# Sheet1.net
KiCad netlist of a schematic drawn in Altium Designer
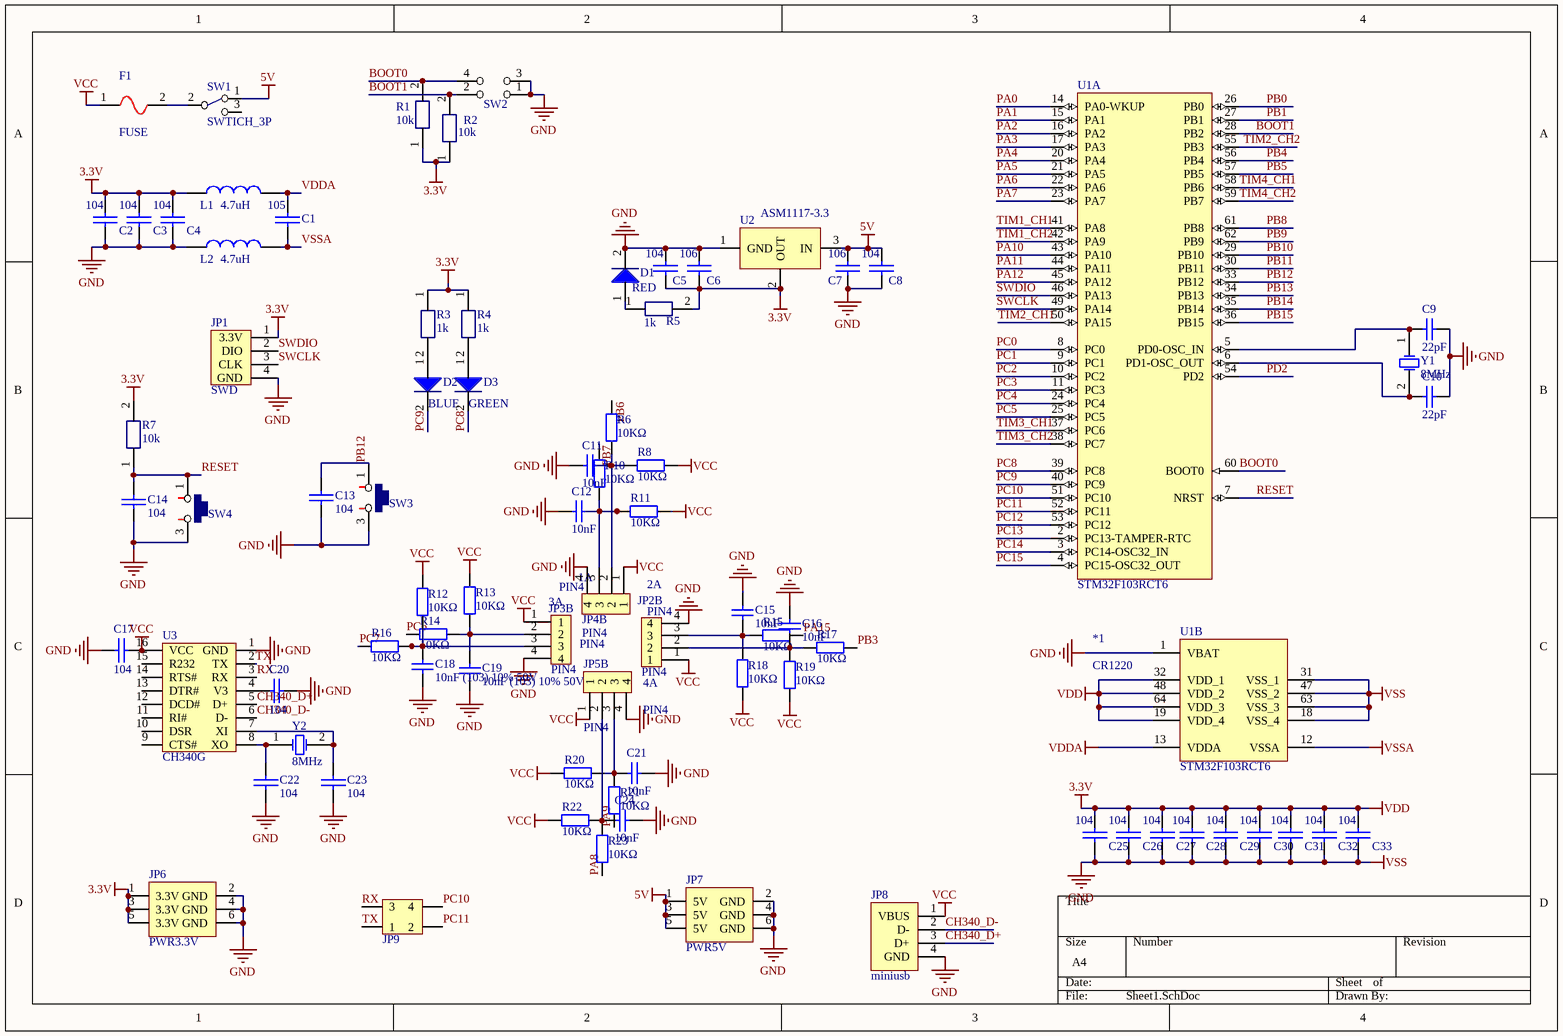
[diagram p0: Sheet1.SchDoc]

(export (version "E")
  (design (tool "Eeschema 10.0.6"))
  (components
    (comp (ref "*1") (value "CR1220") (libsource (lib "Schlib1") (part "CR1220")))
    (comp (ref "1") (value "PIN4") (libsource (lib "") (part "PIN4_2")))
    (comp (ref "2") (value "PIN4") (libsource (lib "") (part "PIN4_1")))
    (comp (ref "3") (value "PIN4") (libsource (lib "编码器Schlib1") (part "PIN4")))
    (comp (ref "4") (value "PIN4") (libsource (lib "") (part "PIN4_2")))
    (comp (ref "C1")
      (value "0805c")
      (footprint "0805C")
      (fields (field (name "ALTIUM_UNNAMED_3") "105"))
      (libsource (lib "CORE") (part "0805c"))
    )
    (comp (ref "C2")
      (value "0805c")
      (footprint "0805C")
      (fields (field (name "ALTIUM_UNNAMED_2") "104"))
      (libsource (lib "CORE") (part "0805c"))
    )
    (comp (ref "C3")
      (value "0805c")
      (footprint "0805C")
      (fields (field (name "ALTIUM_UNNAMED_2") "104"))
      (libsource (lib "CORE") (part "0805c"))
    )
    (comp (ref "C4")
      (value "0805c")
      (footprint "0805C")
      (fields (field (name "ALTIUM_UNNAMED_2") "104"))
      (libsource (lib "CORE") (part "0805c"))
    )
    (comp (ref "C5")
      (value "0805c")
      (footprint "0805C")
      (fields (field (name "ALTIUM_UNNAMED_2") "104"))
      (libsource (lib "CORE") (part "0805c"))
    )
    (comp (ref "C6")
      (value "0805c")
      (footprint "0805C")
      (fields (field (name "ALTIUM_UNNAMED_3") "106"))
      (libsource (lib "CORE") (part "0805c"))
    )
    (comp (ref "C7")
      (value "0805c")
      (footprint "0805C")
      (fields (field (name "ALTIUM_UNNAMED_3") "106"))
      (libsource (lib "CORE") (part "0805c"))
    )
    (comp (ref "C8")
      (value "0805c")
      (footprint "0805C")
      (fields (field (name "ALTIUM_UNNAMED_2") "104"))
      (libsource (lib "CORE") (part "0805c"))
    )
    (comp (ref "C9")
      (value "22pF")
      (footprint "0805C")
      (description "贴片电容")
      (libsource (lib "Cap") (part "0805 22pF (220) 5% 50V"))
    )
    (comp (ref "C10")
      (value "22pF")
      (footprint "0805C")
      (description "贴片电容")
      (libsource (lib "Cap") (part "0805 22pF (220) 5% 50V"))
    )
    (comp (ref "C11")
      (value "10nF")
      (footprint "0805C")
      (description "贴片电容")
      (libsource (lib "Cap") (part "0805 10nF (103) 10% 50V"))
    )
    (comp (ref "C12")
      (value "10nF")
      (footprint "0805C")
      (description "贴片电容")
      (libsource (lib "Cap") (part "0805 10nF (103) 10% 50V"))
    )
    (comp (ref "C13")
      (value "0805c")
      (footprint "0805C")
      (fields (field (name "ALTIUM_UNNAMED_2") "104"))
      (libsource (lib "CORE") (part "0805c"))
    )
    (comp (ref "C14")
      (value "0805c")
      (footprint "0805C")
      (fields (field (name "ALTIUM_UNNAMED_2") "104"))
      (libsource (lib "CORE") (part "0805c"))
    )
    (comp (ref "C15")
      (value "10nF")
      (footprint "0805C")
      (description "贴片电容")
      (libsource (lib "Cap") (part "0805 10nF (103) 10% 50V"))
    )
    (comp (ref "C16")
      (value "10nF")
      (footprint "0805C")
      (description "贴片电容")
      (libsource (lib "Cap") (part "0805 10nF (103) 10% 50V"))
    )
    (comp (ref "C17")
      (value "0805c")
      (footprint "0805C")
      (fields (field (name "ALTIUM_UNNAMED_2") "104"))
      (libsource (lib "CORE") (part "0805c"))
    )
    (comp (ref "C18")
      (value "10nF (103) 10% 50V")
      (footprint "0805C")
      (description "贴片电容")
      (libsource (lib "Cap") (part "0805 10nF (103) 10% 50V"))
    )
    (comp (ref "C19")
      (value "10nF (103) 10% 50V")
      (footprint "0805C")
      (description "贴片电容")
      (libsource (lib "Cap") (part "0805 10nF (103) 10% 50V"))
    )
    (comp (ref "C20")
      (value "0805c")
      (footprint "0805C")
      (fields (field (name "ALTIUM_UNNAMED_2") "104"))
      (libsource (lib "CORE") (part "0805c"))
    )
    (comp (ref "C21")
      (value "10nF")
      (footprint "0805C")
      (description "贴片电容")
      (libsource (lib "Cap") (part "0805 10nF (103) 10% 50V"))
    )
    (comp (ref "C22")
      (value "0805c")
      (footprint "0805C")
      (fields (field (name "ALTIUM_UNNAMED_2") "104"))
      (libsource (lib "CORE") (part "0805c"))
    )
    (comp (ref "C23")
      (value "0805c")
      (footprint "0805C")
      (fields (field (name "ALTIUM_UNNAMED_2") "104"))
      (libsource (lib "CORE") (part "0805c"))
    )
    (comp (ref "C24")
      (value "10nF")
      (footprint "0805C")
      (description "贴片电容")
      (libsource (lib "Cap") (part "0805 10nF (103) 10% 50V"))
    )
    (comp (ref "C25")
      (value "0805c")
      (footprint "0805C")
      (fields (field (name "ALTIUM_UNNAMED_2") "104"))
      (libsource (lib "CORE") (part "0805c"))
    )
    (comp (ref "C26")
      (value "0805c")
      (footprint "0805C")
      (fields (field (name "ALTIUM_UNNAMED_2") "104"))
      (libsource (lib "CORE") (part "0805c"))
    )
    (comp (ref "C27")
      (value "0805c")
      (footprint "0805C")
      (fields (field (name "ALTIUM_UNNAMED_2") "104"))
      (libsource (lib "CORE") (part "0805c"))
    )
    (comp (ref "C28")
      (value "0805c")
      (footprint "0805C")
      (fields (field (name "ALTIUM_UNNAMED_2") "104"))
      (libsource (lib "CORE") (part "0805c"))
    )
    (comp (ref "C29")
      (value "0805c")
      (footprint "0805C")
      (fields (field (name "ALTIUM_UNNAMED_2") "104"))
      (libsource (lib "CORE") (part "0805c"))
    )
    (comp (ref "C30")
      (value "0805c")
      (footprint "0805C")
      (fields (field (name "ALTIUM_UNNAMED_2") "104"))
      (libsource (lib "CORE") (part "0805c"))
    )
    (comp (ref "C31")
      (value "0805c")
      (footprint "0805C")
      (fields (field (name "ALTIUM_UNNAMED_2") "104"))
      (libsource (lib "CORE") (part "0805c"))
    )
    (comp (ref "C32")
      (value "0805c")
      (footprint "0805C")
      (fields (field (name "ALTIUM_UNNAMED_2") "104"))
      (libsource (lib "CORE") (part "0805c"))
    )
    (comp (ref "C33")
      (value "0805c")
      (footprint "0805C")
      (fields (field (name "ALTIUM_UNNAMED_2") "104"))
      (libsource (lib "CORE") (part "0805c"))
    )
    (comp (ref "D1")
      (value "LED")
      (footprint "0805D")
      (fields (field (name "ALTIUM_UNNAMED_1") "RED"))
      (libsource (lib "CORE") (part "LED"))
    )
    (comp (ref "D2")
      (value "LED")
      (footprint "0805D")
      (fields (field (name "ALTIUM_UNNAMED_1") "BLUE"))
      (libsource (lib "CORE") (part "LED"))
    )
    (comp (ref "D3")
      (value "LED")
      (footprint "0805D")
      (fields (field (name "ALTIUM_UNNAMED_1") "GREEN"))
      (libsource (lib "CORE") (part "LED"))
    )
    (comp (ref "F1") (value "FUSE") (footprint "1206R") (libsource (lib "CORE") (part "FUSE")))
    (comp (ref "JP1") (value "SWD") (footprint "SWD") (libsource (lib "CORE") (part "SWD")))
    (comp (ref "JP2") (value "PIN4") (footprint "HDR1X4") (libsource (lib "") (part "PIN4_1")))
    (comp (ref "JP3") (value "PIN4") (footprint "HDR1X4") (libsource (lib "") (part "PIN4_2")))
    (comp (ref "JP4") (value "PIN4") (footprint "HDR1X4") (libsource (lib "编码器Schlib1") (part "PIN4")))
    (comp (ref "JP5") (value "PIN4") (footprint "HDR1X4") (libsource (lib "") (part "PIN4_3")))
    (comp (ref "JP6") (value "PWR3.3V") (footprint "PWR") (libsource (lib "CORE") (part "PWR3.3V")))
    (comp (ref "JP7") (value "PWR5V") (footprint "PWR") (libsource (lib "CORE") (part "PWR5V")))
    (comp (ref "JP8")
      (value "miniusb")
      (footprint "MICRO-USB-SMD_MICROXNJ")
      (libsource (lib "STM32F4") (part "miniusb"))
    )
    (comp (ref "JP9") (value "2*2") (footprint "CON20VP2R54-2X2TM") (libsource (lib "STM32F4") (part "2*2")))
    (comp (ref "L1")
      (value "0805L")
      (footprint "0805L")
      (fields (field (name "ALTIUM_UNNAMED_1") "4.7uH"))
      (libsource (lib "CORE") (part "0805L"))
    )
    (comp (ref "L2")
      (value "0805L")
      (footprint "0805L")
      (fields (field (name "ALTIUM_UNNAMED_1") "4.7uH"))
      (libsource (lib "CORE") (part "0805L"))
    )
    (comp (ref "R1")
      (value "0805r")
      (footprint "0805R")
      (fields (field (name "ALTIUM_UNNAMED_4") "10k"))
      (libsource (lib "CORE") (part "0805r"))
    )
    (comp (ref "R2")
      (value "0805r")
      (footprint "0805R")
      (fields (field (name "ALTIUM_UNNAMED_4") "10k"))
      (libsource (lib "CORE") (part "0805r"))
    )
    (comp (ref "R3")
      (value "0805r")
      (footprint "0805R")
      (fields (field (name "ALTIUM_UNNAMED_3") "1k"))
      (libsource (lib "CORE") (part "0805r"))
    )
    (comp (ref "R4")
      (value "0805r")
      (footprint "0805R")
      (fields (field (name "ALTIUM_UNNAMED_3") "1k"))
      (libsource (lib "CORE") (part "0805r"))
    )
    (comp (ref "R5")
      (value "0805r")
      (footprint "0805R")
      (fields (field (name "ALTIUM_UNNAMED_3") "1k"))
      (libsource (lib "CORE") (part "0805r"))
    )
    (comp (ref "R6")
      (value "10KΩ")
      (footprint "0805R")
      (description "贴片电阻")
      (libsource (lib "") (part "0805 10KΩ (1002) 1%_1"))
    )
    (comp (ref "R7")
      (value "0805r")
      (footprint "0805R")
      (fields (field (name "ALTIUM_UNNAMED_1") "10k"))
      (libsource (lib "CORE") (part "0805r"))
    )
    (comp (ref "R8")
      (value "10KΩ")
      (footprint "0805R")
      (description "贴片电阻")
      (libsource (lib "") (part "0805 10KΩ (1002) 1%_2"))
    )
    (comp (ref "R10")
      (value "10KΩ")
      (footprint "0805R")
      (description "贴片电阻")
      (libsource (lib "") (part "0805 10KΩ (1002) 1%_1"))
    )
    (comp (ref "R11")
      (value "10KΩ")
      (footprint "0805R")
      (description "贴片电阻")
      (libsource (lib "") (part "0805 10KΩ (1002) 1%_2"))
    )
    (comp (ref "R12")
      (value "10KΩ")
      (footprint "0805R")
      (description "贴片电阻")
      (libsource (lib "RES") (part "0805 10KΩ (1002) 1%"))
    )
    (comp (ref "R13")
      (value "10KΩ")
      (footprint "0805R")
      (description "贴片电阻")
      (libsource (lib "") (part "0805 10KΩ (1002) 1%_1"))
    )
    (comp (ref "R14")
      (value "10KΩ")
      (footprint "0805R")
      (description "贴片电阻")
      (libsource (lib "") (part "0805 10KΩ (1002) 1%_3"))
    )
    (comp (ref "R15")
      (value "10KΩ")
      (footprint "0805R")
      (description "贴片电阻")
      (libsource (lib "") (part "0805 10KΩ (1002) 1%_3"))
    )
    (comp (ref "R16")
      (value "10KΩ")
      (footprint "0805R")
      (description "贴片电阻")
      (libsource (lib "") (part "0805 10KΩ (1002) 1%_3"))
    )
    (comp (ref "R17")
      (value "10KΩ")
      (footprint "0805R")
      (description "贴片电阻")
      (libsource (lib "") (part "0805 10KΩ (1002) 1%_3"))
    )
    (comp (ref "R18")
      (value "10KΩ")
      (footprint "0805R")
      (description "贴片电阻")
      (libsource (lib "RES") (part "0805 10KΩ (1002) 1%"))
    )
    (comp (ref "R19")
      (value "10KΩ")
      (footprint "0805R")
      (description "贴片电阻")
      (libsource (lib "") (part "0805 10KΩ (1002) 1%_1"))
    )
    (comp (ref "R20")
      (value "10KΩ")
      (footprint "0805R")
      (description "贴片电阻")
      (libsource (lib "") (part "0805 10KΩ (1002) 1%_3"))
    )
    (comp (ref "R21")
      (value "10KΩ")
      (footprint "0805R")
      (description "贴片电阻")
      (libsource (lib "RES") (part "0805 10KΩ (1002) 1%"))
    )
    (comp (ref "R22")
      (value "10KΩ")
      (footprint "0805R")
      (description "贴片电阻")
      (libsource (lib "") (part "0805 10KΩ (1002) 1%_3"))
    )
    (comp (ref "R23")
      (value "10KΩ")
      (footprint "0805R")
      (description "贴片电阻")
      (libsource (lib "RES") (part "0805 10KΩ (1002) 1%"))
    )
    (comp (ref "SW1") (value "SWTICH_3P") (footprint "SWITCH_3P") (libsource (lib "CORE") (part "SWTICH_3P")))
    (comp (ref "SW2")
      (value "SW_BOOT")
      (footprint "CON20VP2R54-2X2TM")
      (libsource (lib "CORE") (part "SW_BOOT"))
    )
    (comp (ref "SW3")
      (value "KEY")
      (footprint "SW-SMD_L6.1-W3.6-LS8.0")
      (libsource (lib "CORE") (part "KEY_4P"))
    )
    (comp (ref "SW4")
      (value "KEY")
      (footprint "SW-SMD_L6.1-W3.6-LS8.0")
      (libsource (lib "CORE") (part "KEY_4P"))
    )
    (comp (ref "U1")
      (value "STM32F103RCT6")
      (footprint "PCBComponent_1")
      (libsource (lib "STMicroelectronics STM32 F1") (part "STM32F103RCT6"))
    )
    (comp (ref "U2")
      (value "ASM1117-3.3")
      (footprint "SOT223_N")
      (libsource (lib "CORE") (part "ASM1117-3.3"))
    )
    (comp (ref "U3") (value "CH340G") (footprint "SOP16") (libsource (lib "CORE") (part "CH340G")))
    (comp (ref "Y1")
      (value "8MHz")
      (footprint "HC-49US_L11.5-W4.5-P4.88")
      (description "贴片晶振")
      (libsource (lib "CrystalOscillator") (part "SMD-5032_2P 8MHz 20ppm 20pF"))
    )
    (comp (ref "Y2")
      (value "8MHz")
      (footprint "HC-49S_L11.4-W4.8")
      (description "贴片晶振")
      (libsource (lib "CrystalOscillator") (part "SMD-5032_2P 8MHz 20ppm 20pF"))
    )
  )
  (nets
    (net (code "1") (name "/BOOT0") (class "Default")
      (node (ref "R1") (pin "2") (pinfunction "2_2") (pintype "passive"))
      (node (ref "SW2") (pin "4") (pinfunction "4_4") (pintype "passive"))
      (node (ref "U1") (pin "60") (pinfunction "BOOT0_60") (pintype "input"))
    )
    (net (code "2") (name "/BOOT1") (class "Default")
      (node (ref "R2") (pin "2") (pinfunction "2_2") (pintype "passive"))
      (node (ref "SW2") (pin "2") (pinfunction "2_2") (pintype "passive"))
      (node (ref "U1") (pin "28") (pinfunction "PB2_28") (pintype "bidirectional"))
    )
    (net (code "3") (name "/CH340_D+") (class "Default")
      (node (ref "JP8") (pin "3") (pinfunction "D+_3") (pintype "passive"))
      (node (ref "U3") (pin "5") (pinfunction "D+_5") (pintype "passive"))
    )
    (net (code "4") (name "/CH340_D-") (class "Default")
      (node (ref "JP8") (pin "2") (pinfunction "D-_2") (pintype "passive"))
      (node (ref "U3") (pin "6") (pinfunction "D-_6") (pintype "passive"))
    )
    (net (code "5") (name "/PA0") (class "Default")
      (node (ref "U1") (pin "14") (pinfunction "PA0-WKUP_14") (pintype "bidirectional"))
    )
    (net (code "6") (name "/PA1") (class "Default")
      (node (ref "U1") (pin "15") (pinfunction "PA1_15") (pintype "bidirectional"))
    )
    (net (code "7") (name "/PA2") (class "Default")
      (node (ref "U1") (pin "16") (pinfunction "PA2_16") (pintype "bidirectional"))
    )
    (net (code "8") (name "/PA3") (class "Default")
      (node (ref "U1") (pin "17") (pinfunction "PA3_17") (pintype "bidirectional"))
    )
    (net (code "9") (name "/PA4") (class "Default")
      (node (ref "U1") (pin "20") (pinfunction "PA4_20") (pintype "bidirectional"))
    )
    (net (code "10") (name "/PA5") (class "Default")
      (node (ref "U1") (pin "21") (pinfunction "PA5_21") (pintype "bidirectional"))
    )
    (net (code "11") (name "/PA6") (class "Default")
      (node (ref "U1") (pin "22") (pinfunction "PA6_22") (pintype "bidirectional"))
    )
    (net (code "12") (name "/PA7") (class "Default")
      (node (ref "U1") (pin "23") (pinfunction "PA7_23") (pintype "bidirectional"))
    )
    (net (code "13") (name "/PA8") (class "Default")
      (node (ref "R23") (pin "2") (pinfunction "2_2") (pintype "passive"))
    )
    (net (code "14") (name "/PA9") (class "Default")
      (node (ref "R21") (pin "2") (pinfunction "2_2") (pintype "passive"))
    )
    (net (code "15") (name "/PA10") (class "Default")
      (node (ref "U1") (pin "43") (pinfunction "PA10_43") (pintype "bidirectional"))
    )
    (net (code "16") (name "/PA11") (class "Default")
      (node (ref "U1") (pin "44") (pinfunction "PA11_44") (pintype "bidirectional"))
    )
    (net (code "17") (name "/PA12") (class "Default")
      (node (ref "U1") (pin "45") (pinfunction "PA12_45") (pintype "bidirectional"))
    )
    (net (code "18") (name "/PA15") (class "Default")
      (node (ref "R15") (pin "2") (pinfunction "2_2") (pintype "passive"))
    )
    (net (code "19") (name "/PB0") (class "Default")
      (node (ref "U1") (pin "26") (pinfunction "PB0_26") (pintype "bidirectional"))
    )
    (net (code "20") (name "/PB1") (class "Default")
      (node (ref "U1") (pin "27") (pinfunction "PB1_27") (pintype "bidirectional"))
    )
    (net (code "21") (name "/PB3") (class "Default")
      (node (ref "R17") (pin "2") (pinfunction "2_2") (pintype "passive"))
    )
    (net (code "22") (name "/PB4") (class "Default")
      (node (ref "U1") (pin "56") (pinfunction "PB4_56") (pintype "bidirectional"))
    )
    (net (code "23") (name "/PB5") (class "Default")
      (node (ref "U1") (pin "57") (pinfunction "PB5_57") (pintype "bidirectional"))
    )
    (net (code "24") (name "/PB6") (class "Default")
      (node (ref "R6") (pin "2") (pinfunction "2_2") (pintype "passive"))
    )
    (net (code "25") (name "/PB7") (class "Default")
      (node (ref "R10") (pin "2") (pinfunction "2_2") (pintype "passive"))
    )
    (net (code "26") (name "/PB8") (class "Default")
      (node (ref "U1") (pin "61") (pinfunction "PB8_61") (pintype "bidirectional"))
    )
    (net (code "27") (name "/PB9") (class "Default")
      (node (ref "U1") (pin "62") (pinfunction "PB9_62") (pintype "bidirectional"))
    )
    (net (code "28") (name "/PB10") (class "Default")
      (node (ref "U1") (pin "29") (pinfunction "PB10_29") (pintype "bidirectional"))
    )
    (net (code "29") (name "/PB11") (class "Default")
      (node (ref "U1") (pin "30") (pinfunction "PB11_30") (pintype "bidirectional"))
    )
    (net (code "30") (name "/PB12") (class "Default")
      (node (ref "C13") (pin "1") (pinfunction "1_1") (pintype "passive"))
      (node (ref "SW3") (pin "1") (pintype "passive"))
      (node (ref "U1") (pin "33") (pinfunction "PB12_33") (pintype "bidirectional"))
    )
    (net (code "31") (name "/PB13") (class "Default")
      (node (ref "U1") (pin "34") (pinfunction "PB13_34") (pintype "bidirectional"))
    )
    (net (code "32") (name "/PB14") (class "Default")
      (node (ref "U1") (pin "35") (pinfunction "PB14_35") (pintype "bidirectional"))
    )
    (net (code "33") (name "/PB15") (class "Default")
      (node (ref "U1") (pin "36") (pinfunction "PB15_36") (pintype "bidirectional"))
    )
    (net (code "34") (name "/PC0") (class "Default")
      (node (ref "U1") (pin "8") (pinfunction "PC0_8") (pintype "bidirectional"))
    )
    (net (code "35") (name "/PC1") (class "Default")
      (node (ref "U1") (pin "9") (pinfunction "PC1_9") (pintype "bidirectional"))
    )
    (net (code "36") (name "/PC2") (class "Default")
      (node (ref "U1") (pin "10") (pinfunction "PC2_10") (pintype "bidirectional"))
    )
    (net (code "37") (name "/PC3") (class "Default")
      (node (ref "U1") (pin "11") (pinfunction "PC3_11") (pintype "bidirectional"))
    )
    (net (code "38") (name "/PC4") (class "Default")
      (node (ref "U1") (pin "24") (pinfunction "PC4_24") (pintype "bidirectional"))
    )
    (net (code "39") (name "/PC5") (class "Default")
      (node (ref "U1") (pin "25") (pinfunction "PC5_25") (pintype "bidirectional"))
    )
    (net (code "40") (name "/PC6") (class "Default")
      (node (ref "R14") (pin "1") (pinfunction "1_1") (pintype "passive"))
    )
    (net (code "41") (name "/PC7") (class "Default")
      (node (ref "R16") (pin "1") (pinfunction "1_1") (pintype "passive"))
    )
    (net (code "42") (name "/PC8") (class "Default")
      (node (ref "D3") (pin "2") (pinfunction "2_2") (pintype "passive"))
      (node (ref "U1") (pin "39") (pinfunction "PC8_39") (pintype "bidirectional"))
    )
    (net (code "43") (name "/PC9") (class "Default")
      (node (ref "D2") (pin "2") (pinfunction "2_2") (pintype "passive"))
      (node (ref "U1") (pin "40") (pinfunction "PC9_40") (pintype "bidirectional"))
    )
    (net (code "44") (name "/PC10") (class "Default")
      (node (ref "JP9") (pin "4") (pinfunction "4_4") (pintype "passive"))
      (node (ref "U1") (pin "51") (pinfunction "PC10_51") (pintype "bidirectional"))
    )
    (net (code "45") (name "/PC11") (class "Default")
      (node (ref "JP9") (pin "2") (pinfunction "2_2") (pintype "passive"))
      (node (ref "U1") (pin "52") (pinfunction "PC11_52") (pintype "bidirectional"))
    )
    (net (code "46") (name "/PC12") (class "Default")
      (node (ref "U1") (pin "53") (pinfunction "PC12_53") (pintype "bidirectional"))
    )
    (net (code "47") (name "/PC13") (class "Default")
      (node (ref "U1") (pin "2") (pinfunction "PC13-TAMPER-RTC_2") (pintype "bidirectional"))
    )
    (net (code "48") (name "/PC14") (class "Default")
      (node (ref "U1") (pin "3") (pinfunction "PC14-OSC32_IN_3") (pintype "bidirectional"))
    )
    (net (code "49") (name "/PC15") (class "Default")
      (node (ref "U1") (pin "4") (pinfunction "PC15-OSC32_OUT_4") (pintype "bidirectional"))
    )
    (net (code "50") (name "/PD2") (class "Default")
      (node (ref "U1") (pin "54") (pinfunction "PD2_54") (pintype "bidirectional"))
    )
    (net (code "51") (name "/RESET") (class "Default")
      (node (ref "C14") (pin "1") (pinfunction "1_1") (pintype "passive"))
      (node (ref "R7") (pin "1") (pinfunction "1_1") (pintype "passive"))
      (node (ref "SW4") (pin "1") (pintype "passive"))
      (node (ref "U1") (pin "7") (pinfunction "NRST_7") (pintype "bidirectional"))
    )
    (net (code "52") (name "/RX") (class "Default")
      (node (ref "JP9") (pin "3") (pinfunction "3_3") (pintype "passive"))
      (node (ref "U3") (pin "3") (pinfunction "RX_3") (pintype "passive"))
    )
    (net (code "53") (name "/SWCLK") (class "Default")
      (node (ref "JP1") (pin "3") (pinfunction "CLK_3") (pintype "passive"))
      (node (ref "U1") (pin "49") (pinfunction "PA14_49") (pintype "bidirectional"))
    )
    (net (code "54") (name "/SWDIO") (class "Default")
      (node (ref "JP1") (pin "2") (pinfunction "DIO_2") (pintype "passive"))
      (node (ref "U1") (pin "46") (pinfunction "PA13_46") (pintype "bidirectional"))
    )
    (net (code "55") (name "/TIM1_CH1") (class "Default")
      (node (ref "U1") (pin "41") (pinfunction "PA8_41") (pintype "bidirectional"))
    )
    (net (code "56") (name "/TIM1_CH2") (class "Default")
      (node (ref "U1") (pin "42") (pinfunction "PA9_42") (pintype "bidirectional"))
    )
    (net (code "57") (name "/TIM2_CH1") (class "Default")
      (node (ref "U1") (pin "50") (pinfunction "PA15_50") (pintype "bidirectional"))
    )
    (net (code "58") (name "/TIM2_CH2") (class "Default")
      (node (ref "U1") (pin "55") (pinfunction "PB3_55") (pintype "bidirectional"))
    )
    (net (code "59") (name "/TIM3_CH1") (class "Default")
      (node (ref "U1") (pin "37") (pinfunction "PC6_37") (pintype "bidirectional"))
    )
    (net (code "60") (name "/TIM3_CH2") (class "Default")
      (node (ref "U1") (pin "38") (pinfunction "PC7_38") (pintype "bidirectional"))
    )
    (net (code "61") (name "/TIM4_CH1") (class "Default")
      (node (ref "U1") (pin "58") (pinfunction "PB6_58") (pintype "bidirectional"))
    )
    (net (code "62") (name "/TIM4_CH2") (class "Default")
      (node (ref "U1") (pin "59") (pinfunction "PB7_59") (pintype "bidirectional"))
    )
    (net (code "63") (name "/TX") (class "Default")
      (node (ref "JP9") (pin "1") (pinfunction "1_1") (pintype "passive"))
      (node (ref "U3") (pin "2") (pinfunction "TX_2") (pintype "passive"))
    )
    (net (code "64") (name "3.3V") (class "Default")
      (node (ref "C2") (pin "1") (pinfunction "1_1") (pintype "passive"))
      (node (ref "C25") (pin "1") (pinfunction "1_1") (pintype "passive"))
      (node (ref "C26") (pin "1") (pinfunction "1_1") (pintype "passive"))
      (node (ref "C27") (pin "1") (pinfunction "1_1") (pintype "passive"))
      (node (ref "C28") (pin "1") (pinfunction "1_1") (pintype "passive"))
      (node (ref "C29") (pin "1") (pinfunction "1_1") (pintype "passive"))
      (node (ref "C3") (pin "1") (pinfunction "1_1") (pintype "passive"))
      (node (ref "C30") (pin "1") (pinfunction "1_1") (pintype "passive"))
      (node (ref "C31") (pin "1") (pinfunction "1_1") (pintype "passive"))
      (node (ref "C32") (pin "1") (pinfunction "1_1") (pintype "passive"))
      (node (ref "C33") (pin "1") (pinfunction "1_1") (pintype "passive"))
      (node (ref "C4") (pin "1") (pinfunction "1_1") (pintype "passive"))
      (node (ref "C5") (pin "2") (pinfunction "2_2") (pintype "passive"))
      (node (ref "C6") (pin "2") (pinfunction "2_2") (pintype "passive"))
      (node (ref "JP1") (pin "1") (pinfunction "3.3V_1") (pintype "passive"))
      (node (ref "JP6") (pin "1") (pinfunction "3.3V_1") (pintype "passive"))
      (node (ref "JP6") (pin "3") (pinfunction "3.3V_3") (pintype "passive"))
      (node (ref "JP6") (pin "5") (pinfunction "3.3V_5") (pintype "passive"))
      (node (ref "L1") (pin "1") (pinfunction "1_1") (pintype "passive"))
      (node (ref "R1") (pin "1") (pinfunction "1_1") (pintype "passive"))
      (node (ref "R2") (pin "1") (pinfunction "1_1") (pintype "passive"))
      (node (ref "R3") (pin "1") (pinfunction "1_1") (pintype "passive"))
      (node (ref "R4") (pin "1") (pinfunction "1_1") (pintype "passive"))
      (node (ref "R5") (pin "2") (pinfunction "2_2") (pintype "passive"))
      (node (ref "R7") (pin "2") (pinfunction "2_2") (pintype "passive"))
      (node (ref "U1") (pin "19") (pinfunction "VDD_4_19") (pintype "power_in"))
      (node (ref "U1") (pin "32") (pinfunction "VDD_1_32") (pintype "power_in"))
      (node (ref "U1") (pin "48") (pinfunction "VDD_2_48") (pintype "power_in"))
      (node (ref "U1") (pin "64") (pinfunction "VDD_3_64") (pintype "power_in"))
      (node (ref "U2") (pin "2") (pinfunction "OUT_2") (pintype "passive"))
    )
    (net (code "65") (name "5V") (class "Default")
      (node (ref "C7") (pin "1") (pinfunction "1_1") (pintype "passive"))
      (node (ref "C8") (pin "1") (pinfunction "1_1") (pintype "passive"))
      (node (ref "JP7") (pin "1") (pinfunction "5V_1") (pintype "passive"))
      (node (ref "JP7") (pin "3") (pinfunction "5V_3") (pintype "passive"))
      (node (ref "JP7") (pin "5") (pinfunction "5V_5") (pintype "passive"))
      (node (ref "SW1") (pin "1") (pinfunction "1_1") (pintype "passive"))
      (node (ref "U2") (pin "3") (pinfunction "IN_3") (pintype "passive"))
    )
    (net (code "66") (name "GND") (class "Default")
      (node (ref "C10") (pin "2") (pinfunction "2_2") (pintype "passive"))
      (node (ref "C11") (pin "1") (pinfunction "1_1") (pintype "passive"))
      (node (ref "C12") (pin "1") (pinfunction "1_1") (pintype "passive"))
      (node (ref "C13") (pin "2") (pinfunction "2_2") (pintype "passive"))
      (node (ref "C14") (pin "2") (pinfunction "2_2") (pintype "passive"))
      (node (ref "C15") (pin "1") (pinfunction "1_1") (pintype "passive"))
      (node (ref "C16") (pin "2") (pinfunction "2_2") (pintype "passive"))
      (node (ref "C17") (pin "1") (pinfunction "1_1") (pintype "passive"))
      (node (ref "C18") (pin "2") (pinfunction "2_2") (pintype "passive"))
      (node (ref "C19") (pin "2") (pinfunction "2_2") (pintype "passive"))
      (node (ref "C2") (pin "2") (pinfunction "2_2") (pintype "passive"))
      (node (ref "C20") (pin "2") (pinfunction "2_2") (pintype "passive"))
      (node (ref "C21") (pin "2") (pinfunction "2_2") (pintype "passive"))
      (node (ref "C22") (pin "2") (pinfunction "2_2") (pintype "passive"))
      (node (ref "C23") (pin "2") (pinfunction "2_2") (pintype "passive"))
      (node (ref "C24") (pin "2") (pinfunction "2_2") (pintype "passive"))
      (node (ref "C25") (pin "2") (pinfunction "2_2") (pintype "passive"))
      (node (ref "C26") (pin "2") (pinfunction "2_2") (pintype "passive"))
      (node (ref "C27") (pin "2") (pinfunction "2_2") (pintype "passive"))
      (node (ref "C28") (pin "2") (pinfunction "2_2") (pintype "passive"))
      (node (ref "C29") (pin "2") (pinfunction "2_2") (pintype "passive"))
      (node (ref "C3") (pin "2") (pinfunction "2_2") (pintype "passive"))
      (node (ref "C30") (pin "2") (pinfunction "2_2") (pintype "passive"))
      (node (ref "C31") (pin "2") (pinfunction "2_2") (pintype "passive"))
      (node (ref "C32") (pin "2") (pinfunction "2_2") (pintype "passive"))
      (node (ref "C33") (pin "2") (pinfunction "2_2") (pintype "passive"))
      (node (ref "C4") (pin "2") (pinfunction "2_2") (pintype "passive"))
      (node (ref "C5") (pin "1") (pinfunction "1_1") (pintype "passive"))
      (node (ref "C6") (pin "1") (pinfunction "1_1") (pintype "passive"))
      (node (ref "C7") (pin "2") (pinfunction "2_2") (pintype "passive"))
      (node (ref "C8") (pin "2") (pinfunction "2_2") (pintype "passive"))
      (node (ref "C9") (pin "2") (pinfunction "2_2") (pintype "passive"))
      (node (ref "D1") (pin "2") (pinfunction "2_2") (pintype "passive"))
      (node (ref "JP1") (pin "4") (pinfunction "GND_4") (pintype "passive"))
      (node (ref "JP2") (pin "4") (pinfunction "4_4") (pintype "passive"))
      (node (ref "JP3") (pin "4") (pinfunction "4_4") (pintype "passive"))
      (node (ref "JP4") (pin "4") (pinfunction "4_4") (pintype "passive"))
      (node (ref "JP5") (pin "4") (pinfunction "4_4") (pintype "passive"))
      (node (ref "JP6") (pin "2") (pinfunction "GND_2") (pintype "passive"))
      (node (ref "JP6") (pin "4") (pinfunction "GND_4") (pintype "passive"))
      (node (ref "JP6") (pin "6") (pinfunction "GND_6") (pintype "passive"))
      (node (ref "JP7") (pin "2") (pinfunction "GND_2") (pintype "passive"))
      (node (ref "JP7") (pin "4") (pinfunction "GND_4") (pintype "passive"))
      (node (ref "JP7") (pin "6") (pinfunction "GND_6") (pintype "passive"))
      (node (ref "JP8") (pin "4") (pinfunction "GND_4") (pintype "passive"))
      (node (ref "L2") (pin "1") (pinfunction "1_1") (pintype "passive"))
      (node (ref "SW2") (pin "1") (pinfunction "1_1") (pintype "passive"))
      (node (ref "SW2") (pin "3") (pinfunction "3_3") (pintype "passive"))
      (node (ref "SW3") (pin "3") (pintype "passive"))
      (node (ref "SW4") (pin "3") (pintype "passive"))
      (node (ref "U1") (pin "1") (pinfunction "VBAT_1") (pintype "power_in"))
      (node (ref "U1") (pin "18") (pinfunction "VSS_4_18") (pintype "power_in"))
      (node (ref "U1") (pin "31") (pinfunction "VSS_1_31") (pintype "power_in"))
      (node (ref "U1") (pin "47") (pinfunction "VSS_2_47") (pintype "power_in"))
      (node (ref "U1") (pin "63") (pinfunction "VSS_3_63") (pintype "power_in"))
      (node (ref "U2") (pin "1") (pinfunction "GND_1") (pintype "passive"))
      (node (ref "U3") (pin "1") (pinfunction "GND_1") (pintype "passive"))
    )
    (net (code "67") (name "Net-(C11-Pad2)") (class "Default")
      (node (ref "C11") (pin "2") (pinfunction "2_2") (pintype "passive"))
      (node (ref "JP4") (pin "2") (pinfunction "2_2") (pintype "passive"))
      (node (ref "R6") (pin "1") (pinfunction "1_1") (pintype "passive"))
      (node (ref "R8") (pin "2") (pinfunction "2_2") (pintype "passive"))
    )
    (net (code "68") (name "Net-(C12-Pad2)") (class "Default")
      (node (ref "C12") (pin "2") (pinfunction "2_2") (pintype "passive"))
      (node (ref "JP4") (pin "3") (pinfunction "3_3") (pintype "passive"))
      (node (ref "R10") (pin "1") (pinfunction "1_1") (pintype "passive"))
      (node (ref "R11") (pin "2") (pinfunction "2_2") (pintype "passive"))
    )
    (net (code "69") (name "Net-(C18-Pad1)") (class "Default")
      (node (ref "C18") (pin "1") (pinfunction "1_1") (pintype "passive"))
      (node (ref "JP3") (pin "3") (pinfunction "3_3") (pintype "passive"))
      (node (ref "R12") (pin "2") (pinfunction "2_2") (pintype "passive"))
      (node (ref "R16") (pin "2") (pinfunction "2_2") (pintype "passive"))
    )
    (net (code "70") (name "Net-(C19-Pad1)") (class "Default")
      (node (ref "C19") (pin "1") (pinfunction "1_1") (pintype "passive"))
      (node (ref "JP3") (pin "2") (pinfunction "2_2") (pintype "passive"))
      (node (ref "R13") (pin "1") (pinfunction "1_1") (pintype "passive"))
      (node (ref "R14") (pin "2") (pinfunction "2_2") (pintype "passive"))
    )
    (net (code "71") (name "Net-(C21-Pad1)") (class "Default")
      (node (ref "C21") (pin "1") (pinfunction "1_1") (pintype "passive"))
      (node (ref "JP5") (pin "3") (pinfunction "3_3") (pintype "passive"))
      (node (ref "R20") (pin "2") (pinfunction "2_2") (pintype "passive"))
      (node (ref "R21") (pin "1") (pinfunction "1_1") (pintype "passive"))
    )
    (net (code "72") (name "Net-(C24-Pad1)") (class "Default")
      (node (ref "C24") (pin "1") (pinfunction "1_1") (pintype "passive"))
      (node (ref "JP5") (pin "2") (pinfunction "2_2") (pintype "passive"))
      (node (ref "R22") (pin "2") (pinfunction "2_2") (pintype "passive"))
      (node (ref "R23") (pin "1") (pinfunction "1_1") (pintype "passive"))
    )
    (net (code "73") (name "Net-(D1-Pad1)") (class "Default")
      (node (ref "D1") (pin "1") (pinfunction "1_1") (pintype "passive"))
      (node (ref "R5") (pin "1") (pinfunction "1_1") (pintype "passive"))
    )
    (net (code "74") (name "Net-(D2-Pad1)") (class "Default")
      (node (ref "D2") (pin "1") (pinfunction "1_1") (pintype "passive"))
      (node (ref "R3") (pin "2") (pinfunction "2_2") (pintype "passive"))
    )
    (net (code "75") (name "Net-(D3-Pad1)") (class "Default")
      (node (ref "D3") (pin "1") (pinfunction "1_1") (pintype "passive"))
      (node (ref "R4") (pin "2") (pinfunction "2_2") (pintype "passive"))
    )
    (net (code "76") (name "Net-(F1-Pad2)") (class "Default")
      (node (ref "F1") (pin "2") (pinfunction "2_2") (pintype "passive"))
      (node (ref "SW1") (pin "2") (pinfunction "2_2") (pintype "passive"))
    )
    (net (code "77") (name "Net-(JP2-Pad2)") (class "Default")
      (node (ref "JP2") (pin "2") (pinfunction "2_2") (pintype "passive"))
      (node (ref "R17") (pin "1") (pinfunction "1_1") (pintype "passive"))
      (node (ref "R19") (pin "2") (pinfunction "2_2") (pintype "passive"))
    )
    (net (code "78") (name "Net-(JP2-Pad3)") (class "Default")
      (node (ref "JP2") (pin "3") (pinfunction "3_3") (pintype "passive"))
      (node (ref "R15") (pin "1") (pinfunction "1_1") (pintype "passive"))
      (node (ref "R18") (pin "1") (pinfunction "1_1") (pintype "passive"))
    )
    (net (code "79") (name "Net-(U1A-PD0-OSC_IN)") (class "Default")
      (node (ref "C9") (pin "1") (pinfunction "1_1") (pintype "passive"))
      (node (ref "U1") (pin "5") (pinfunction "PD0-OSC_IN_5") (pintype "bidirectional"))
      (node (ref "Y1") (pin "1") (pinfunction "OSC1_1") (pintype "passive"))
    )
    (net (code "80") (name "Net-(U1A-PD1-OSC_OUT)") (class "Default")
      (node (ref "C10") (pin "1") (pinfunction "1_1") (pintype "passive"))
      (node (ref "U1") (pin "6") (pinfunction "PD1-OSC_OUT_6") (pintype "bidirectional"))
      (node (ref "Y1") (pin "2") (pinfunction "OSC2_2") (pintype "passive"))
    )
    (net (code "81") (name "Net-(U3-V3)") (class "Default")
      (node (ref "C20") (pin "1") (pinfunction "1_1") (pintype "passive"))
      (node (ref "U3") (pin "4") (pinfunction "V3_4") (pintype "passive"))
    )
    (net (code "82") (name "Net-(U3-XI)") (class "Default")
      (node (ref "C23") (pin "1") (pinfunction "1_1") (pintype "passive"))
      (node (ref "U3") (pin "7") (pinfunction "XI_7") (pintype "passive"))
      (node (ref "Y2") (pin "2") (pinfunction "OSC2_2") (pintype "passive"))
    )
    (net (code "83") (name "Net-(U3-XO)") (class "Default")
      (node (ref "C22") (pin "1") (pinfunction "1_1") (pintype "passive"))
      (node (ref "U3") (pin "8") (pinfunction "XO_8") (pintype "passive"))
      (node (ref "Y2") (pin "1") (pinfunction "OSC1_1") (pintype "passive"))
    )
    (net (code "84") (name "VCC") (class "Default")
      (node (ref "C17") (pin "2") (pinfunction "2_2") (pintype "passive"))
      (node (ref "F1") (pin "1") (pinfunction "1_1") (pintype "passive"))
      (node (ref "JP2") (pin "1") (pinfunction "1_1") (pintype "passive"))
      (node (ref "JP3") (pin "1") (pinfunction "1_1") (pintype "passive"))
      (node (ref "JP4") (pin "1") (pinfunction "1_1") (pintype "passive"))
      (node (ref "JP5") (pin "1") (pinfunction "1_1") (pintype "passive"))
      (node (ref "JP8") (pin "1") (pinfunction "VBUS_1") (pintype "passive"))
      (node (ref "R11") (pin "1") (pinfunction "1_1") (pintype "passive"))
      (node (ref "R12") (pin "1") (pinfunction "1_1") (pintype "passive"))
      (node (ref "R13") (pin "2") (pinfunction "2_2") (pintype "passive"))
      (node (ref "R18") (pin "2") (pinfunction "2_2") (pintype "passive"))
      (node (ref "R19") (pin "1") (pinfunction "1_1") (pintype "passive"))
      (node (ref "R20") (pin "1") (pinfunction "1_1") (pintype "passive"))
      (node (ref "R22") (pin "1") (pinfunction "1_1") (pintype "passive"))
      (node (ref "R8") (pin "1") (pinfunction "1_1") (pintype "passive"))
      (node (ref "U3") (pin "16") (pinfunction "VCC_16") (pintype "passive"))
    )
    (net (code "85") (name "VDDA") (class "Default")
      (node (ref "C1") (pin "1") (pinfunction "1_1") (pintype "passive"))
      (node (ref "L1") (pin "2") (pinfunction "2_2") (pintype "passive"))
      (node (ref "U1") (pin "13") (pinfunction "VDDA_13") (pintype "power_in"))
    )
    (net (code "86") (name "VSSA") (class "Default")
      (node (ref "C1") (pin "2") (pinfunction "2_2") (pintype "passive"))
      (node (ref "L2") (pin "2") (pinfunction "2_2") (pintype "passive"))
      (node (ref "U1") (pin "12") (pinfunction "VSSA_12") (pintype "power_in"))
    )
    (net (code "87") (name "unconnected-(C15-Pad2)") (class "Default")
      (node (ref "C15") (pin "2") (pinfunction "2_2") (pintype "passive"))
    )
    (net (code "88") (name "unconnected-(C16-Pad1)") (class "Default")
      (node (ref "C16") (pin "1") (pinfunction "1_1") (pintype "passive"))
    )
    (net (code "89") (name "unconnected-(SW1-Pad3)") (class "Default")
      (node (ref "SW1") (pin "3") (pinfunction "3_3") (pintype "passive"))
    )
    (net (code "90") (name "unconnected-(U3-CTS#-Pad9)") (class "Default")
      (node (ref "U3") (pin "9") (pinfunction "CTS#_9") (pintype "passive"))
    )
    (net (code "91") (name "unconnected-(U3-DCD#-Pad12)") (class "Default")
      (node (ref "U3") (pin "12") (pinfunction "DCD#_12") (pintype "passive"))
    )
    (net (code "92") (name "unconnected-(U3-DSR-Pad10)") (class "Default")
      (node (ref "U3") (pin "10") (pinfunction "DSR_10") (pintype "passive"))
    )
    (net (code "93") (name "unconnected-(U3-DTR#-Pad13)") (class "Default")
      (node (ref "U3") (pin "13") (pinfunction "DTR#_13") (pintype "passive"))
    )
    (net (code "94") (name "unconnected-(U3-R232-Pad15)") (class "Default")
      (node (ref "U3") (pin "15") (pinfunction "R232_15") (pintype "passive"))
    )
    (net (code "95") (name "unconnected-(U3-RI#-Pad11)") (class "Default")
      (node (ref "U3") (pin "11") (pinfunction "RI#_11") (pintype "passive"))
    )
    (net (code "96") (name "unconnected-(U3-RTS#-Pad14)") (class "Default")
      (node (ref "U3") (pin "14") (pinfunction "RTS#_14") (pintype "passive"))
    )
  )
)
